# DC-Brush-Motor.net
KiCad netlist of a schematic drawn in Altium Designer
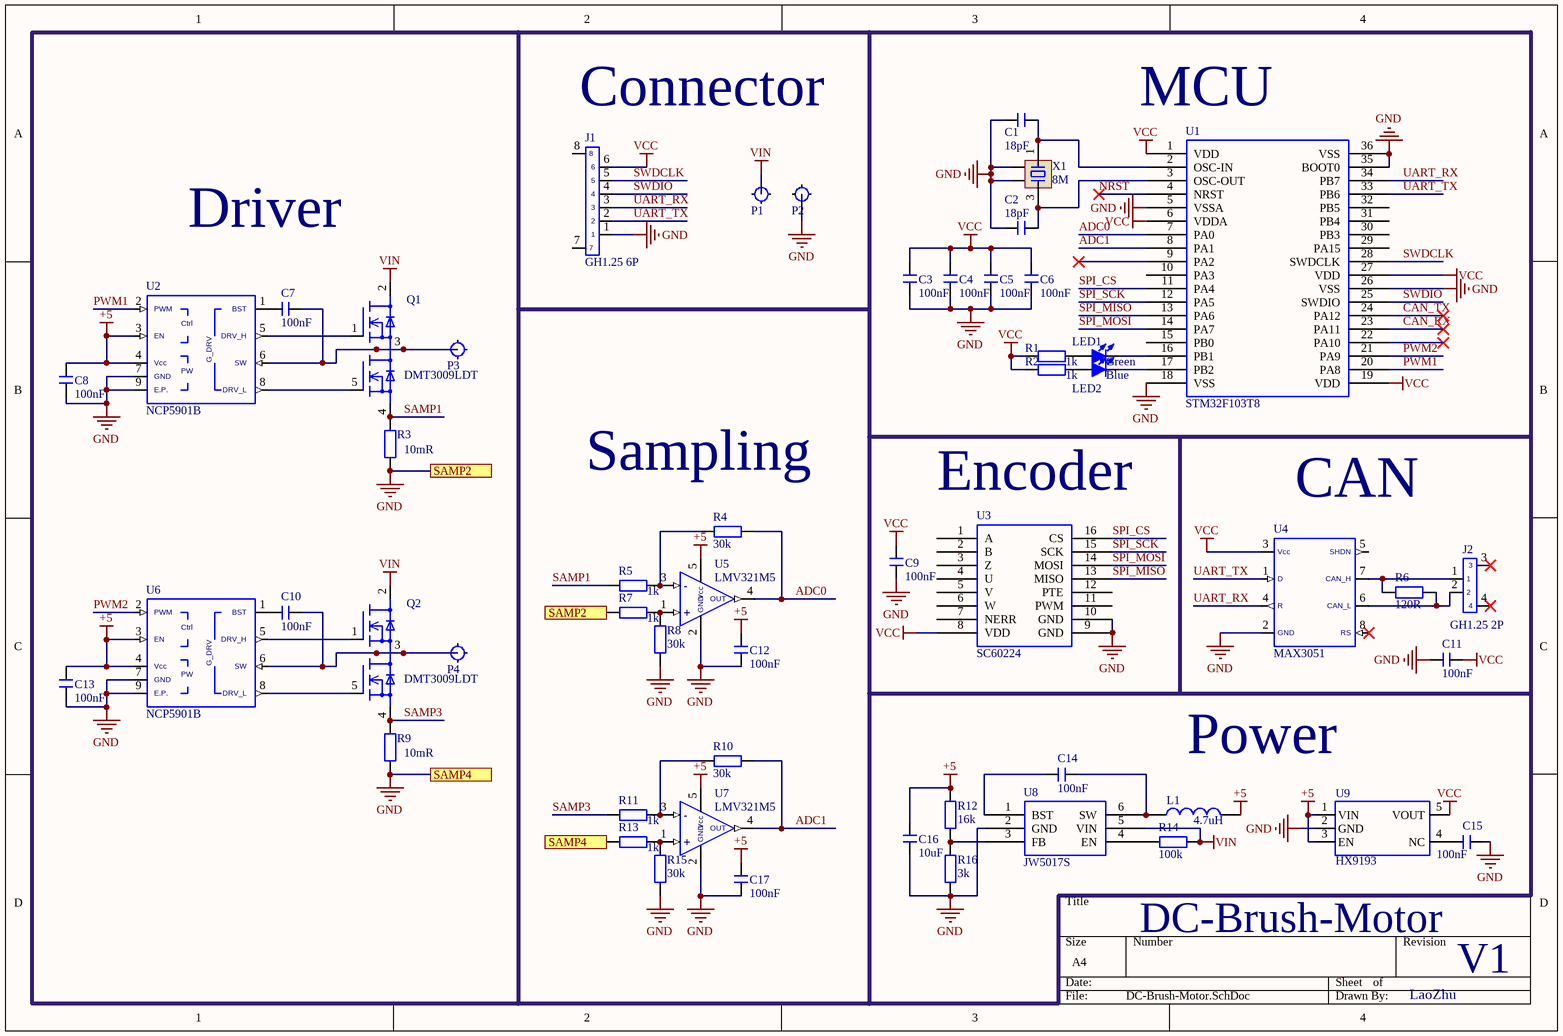
[diagram p0: DC-Brush-Motor.SchDoc]

(export (version "E")
  (design (tool "Eeschema 10.0.6"))
  (components
    (comp (ref "C1")
      (value "18pF")
      (footprint "C 0603")
      (description "无极性贴片电容")
      (fields (field (name "Comment") "C"))
      (libsource (lib "电阻-电容-电感") (part "C"))
    )
    (comp (ref "C2")
      (value "18pF")
      (footprint "C 0603")
      (description "无极性贴片电容")
      (fields (field (name "Comment") "C"))
      (libsource (lib "电阻-电容-电感") (part "C"))
    )
    (comp (ref "C3")
      (value "100nF")
      (footprint "C 0603")
      (description "无极性贴片电容")
      (fields (field (name "Comment") "C"))
      (libsource (lib "电阻-电容-电感") (part "C"))
    )
    (comp (ref "C4")
      (value "100nF")
      (footprint "C 0603")
      (description "无极性贴片电容")
      (fields (field (name "Comment") "C"))
      (libsource (lib "电阻-电容-电感") (part "C"))
    )
    (comp (ref "C5")
      (value "100nF")
      (footprint "C 0603")
      (description "无极性贴片电容")
      (fields (field (name "Comment") "C"))
      (libsource (lib "电阻-电容-电感") (part "C"))
    )
    (comp (ref "C6")
      (value "100nF")
      (footprint "C 0603")
      (description "无极性贴片电容")
      (fields (field (name "Comment") "C"))
      (libsource (lib "电阻-电容-电感") (part "C"))
    )
    (comp (ref "C7")
      (value "100nF")
      (footprint "C 0603")
      (description "无极性贴片电容")
      (fields (field (name "Comment") "C"))
      (libsource (lib "电阻-电容-电感") (part "C"))
    )
    (comp (ref "C8")
      (value "100nF")
      (footprint "C 0603")
      (description "无极性贴片电容")
      (fields (field (name "Comment") "C"))
      (libsource (lib "电阻-电容-电感") (part "C"))
    )
    (comp (ref "C9")
      (value "100nF")
      (footprint "C 0603")
      (description "无极性贴片电容")
      (fields (field (name "Comment") "C"))
      (libsource (lib "电阻-电容-电感") (part "C"))
    )
    (comp (ref "C10")
      (value "100nF")
      (footprint "C 0603")
      (description "无极性贴片电容")
      (fields (field (name "Comment") "C"))
      (libsource (lib "电阻-电容-电感") (part "C"))
    )
    (comp (ref "C11")
      (value "100nF")
      (footprint "C 0603")
      (description "无极性贴片电容")
      (fields (field (name "Comment") "C"))
      (libsource (lib "电阻-电容-电感") (part "C"))
    )
    (comp (ref "C12")
      (value "100nF")
      (footprint "C 0603")
      (description "无极性贴片电容")
      (fields (field (name "Comment") "C"))
      (libsource (lib "电阻-电容-电感") (part "C"))
    )
    (comp (ref "C13")
      (value "100nF")
      (footprint "C 0603")
      (description "无极性贴片电容")
      (fields (field (name "Comment") "C"))
      (libsource (lib "电阻-电容-电感") (part "C"))
    )
    (comp (ref "C14")
      (value "100nF")
      (footprint "C 0603")
      (description "无极性贴片电容")
      (fields (field (name "Comment") "C"))
      (libsource (lib "电阻-电容-电感") (part "C"))
    )
    (comp (ref "C15")
      (value "100nF")
      (footprint "C 0603")
      (description "无极性贴片电容")
      (fields (field (name "Comment") "C"))
      (libsource (lib "电阻-电容-电感") (part "C"))
    )
    (comp (ref "C16")
      (value "10uF")
      (footprint "C 0603")
      (description "无极性贴片电容")
      (fields (field (name "Comment") "C"))
      (libsource (lib "电阻-电容-电感") (part "C"))
    )
    (comp (ref "C17")
      (value "100nF")
      (footprint "C 0603")
      (description "无极性贴片电容")
      (fields (field (name "Comment") "C"))
      (libsource (lib "电阻-电容-电感") (part "C"))
    )
    (comp (ref "J1")
      (value "GH1.25 6P")
      (footprint "GH1.25-6P")
      (libsource (lib "ADlib @LAN") (part "CON_GH1.25_6P"))
    )
    (comp (ref "J2")
      (value "GH1.25 2P")
      (footprint "GH1.25-2P")
      (libsource (lib "ADlib @LAN") (part "CON_GH1.25_2P"))
    )
    (comp (ref "L1")
      (value "4.7uH")
      (footprint "M2520L")
      (description "小功率贴片电感")
      (fields (field (name "Comment") "L"))
      (libsource (lib "电阻-电容-电感") (part "L"))
    )
    (comp (ref "LED1")
      (value "Green")
      (footprint "LED 0603W")
      (description "贴片LED")
      (fields (field (name "版权归属") "源创客"))
      (libsource (lib "LED") (part "LED-SMD"))
    )
    (comp (ref "LED2")
      (value "Blue")
      (footprint "LED 0603W")
      (description "贴片LED")
      (fields (field (name "版权归属") "源创客"))
      (libsource (lib "LED") (part "LED-SMD"))
    )
    (comp (ref "P1")
      (value "CON_Single")
      (footprint "SIG_PAD")
      (libsource (lib "ADlib @LAN") (part "CON_Single"))
    )
    (comp (ref "P2")
      (value "CON_Single")
      (footprint "SIG_PAD")
      (libsource (lib "ADlib @LAN") (part "CON_Single"))
    )
    (comp (ref "P3")
      (value "CON_Single")
      (footprint "4.8MM 冷压端子")
      (libsource (lib "ADlib @LAN") (part "CON_Single"))
    )
    (comp (ref "P4")
      (value "CON_Single")
      (footprint "4.8MM 冷压端子")
      (libsource (lib "ADlib @LAN") (part "CON_Single"))
    )
    (comp (ref "Q1")
      (value "DMT3009LDT")
      (footprint "DFN-8 3X3 (TYPE-K)")
      (libsource (lib "ADlib @LAN") (part "Q_FET_Nx2"))
    )
    (comp (ref "Q2")
      (value "DMT3009LDT")
      (footprint "DFN-8 3X3 (TYPE-K)")
      (libsource (lib "ADlib @LAN") (part "Q_FET_Nx2"))
    )
    (comp (ref "R1")
      (value "1k")
      (footprint "R 0603")
      (description "贴片电阻")
      (fields (field (name "Comment") "R"))
      (libsource (lib "电阻-电容-电感") (part "R"))
    )
    (comp (ref "R2")
      (value "1k")
      (footprint "R 0603")
      (description "贴片电阻")
      (fields (field (name "Comment") "R"))
      (libsource (lib "电阻-电容-电感") (part "R"))
    )
    (comp (ref "R3")
      (value "10mR")
      (footprint "R 1206-HP")
      (description "贴片电阻")
      (fields (field (name "Comment") "R"))
      (libsource (lib "电阻-电容-电感") (part "R"))
    )
    (comp (ref "R4")
      (value "30k")
      (footprint "R 0603")
      (description "贴片电阻")
      (fields (field (name "Comment") "R"))
      (libsource (lib "电阻-电容-电感") (part "R"))
    )
    (comp (ref "R5")
      (value "1k")
      (footprint "R 0603")
      (description "贴片电阻")
      (fields (field (name "Comment") "R"))
      (libsource (lib "电阻-电容-电感") (part "R"))
    )
    (comp (ref "R6")
      (value "120R")
      (footprint "R 0603")
      (description "贴片电阻")
      (fields (field (name "Comment") "R"))
      (libsource (lib "电阻-电容-电感") (part "R"))
    )
    (comp (ref "R7")
      (value "1k")
      (footprint "R 0603")
      (description "贴片电阻")
      (fields (field (name "Comment") "R"))
      (libsource (lib "电阻-电容-电感") (part "R"))
    )
    (comp (ref "R8")
      (value "30k")
      (footprint "R 0603")
      (description "贴片电阻")
      (fields (field (name "Comment") "R"))
      (libsource (lib "电阻-电容-电感") (part "R"))
    )
    (comp (ref "R9")
      (value "10mR")
      (footprint "R 1206-HP")
      (description "贴片电阻")
      (fields (field (name "Comment") "R"))
      (libsource (lib "电阻-电容-电感") (part "R"))
    )
    (comp (ref "R10")
      (value "30k")
      (footprint "R 0603")
      (description "贴片电阻")
      (fields (field (name "Comment") "R"))
      (libsource (lib "电阻-电容-电感") (part "R"))
    )
    (comp (ref "R11")
      (value "1k")
      (footprint "R 0603")
      (description "贴片电阻")
      (fields (field (name "Comment") "R"))
      (libsource (lib "电阻-电容-电感") (part "R"))
    )
    (comp (ref "R12")
      (value "16k")
      (footprint "R 0603")
      (description "贴片电阻")
      (fields (field (name "Comment") "R"))
      (libsource (lib "电阻-电容-电感") (part "R"))
    )
    (comp (ref "R13")
      (value "1k")
      (footprint "R 0603")
      (description "贴片电阻")
      (fields (field (name "Comment") "R"))
      (libsource (lib "电阻-电容-电感") (part "R"))
    )
    (comp (ref "R14")
      (value "100k")
      (footprint "R 0603")
      (description "贴片电阻")
      (fields (field (name "Comment") "R"))
      (libsource (lib "电阻-电容-电感") (part "R"))
    )
    (comp (ref "R15")
      (value "30k")
      (footprint "R 0603")
      (description "贴片电阻")
      (fields (field (name "Comment") "R"))
      (libsource (lib "电阻-电容-电感") (part "R"))
    )
    (comp (ref "R16")
      (value "3k")
      (footprint "R 0603")
      (description "贴片电阻")
      (fields (field (name "Comment") "R"))
      (libsource (lib "电阻-电容-电感") (part "R"))
    )
    (comp (ref "U1")
      (value "STM32F103T8")
      (footprint "QFN-36")
      (libsource (lib "Acme-FOC-V1") (part "STM32F103T8"))
    )
    (comp (ref "U2")
      (value "NCP5901B")
      (footprint "DFN-8")
      (libsource (lib "ADlib @LAN") (part "U_FETs_DVR"))
    )
    (comp (ref "U3") (value "SC60224") (footprint "SSOP16") (libsource (lib "Acme-FOC-V1") (part "SC60224")))
    (comp (ref "U4")
      (value "MAX3051")
      (footprint "SOT23-8L")
      (libsource (lib "ADlib @LAN") (part "U_CAN_TRANS#1"))
    )
    (comp (ref "U5") (value "LMV321M5") (footprint "SOT23-5L") (libsource (lib "ADlib @LAN") (part "U_AMP")))
    (comp (ref "U6")
      (value "NCP5901B")
      (footprint "DFN-8")
      (libsource (lib "ADlib @LAN") (part "U_FETs_DVR"))
    )
    (comp (ref "U7") (value "LMV321M5") (footprint "SOT23-5N") (libsource (lib "ADlib @LAN") (part "U_AMP")))
    (comp (ref "U8")
      (value "JW5017S")
      (footprint "SOT23-6L")
      (libsource (lib "Acme-FOC-V1") (part "JW5017S"))
    )
    (comp (ref "U9")
      (value "HX9193")
      (footprint "SOT23-5L")
      (description "Buck降压芯片")
      (libsource (lib "IC芯片") (part "HX9193"))
    )
    (comp (ref "X1")
      (value "8M")
      (footprint "XTAL-3225")
      (description "4脚晶振")
      (fields (field (name "版权归属") "源创客"))
      (libsource (lib "保险丝-晶振") (part "XTAL-4"))
    )
  )
  (nets
    (net (code "1") (name "+5") (class "Default")
      (node (ref "C12") (pin "2") (pinfunction "2_2") (pintype "passive"))
      (node (ref "C13") (pin "2") (pinfunction "2_2") (pintype "passive"))
      (node (ref "C16") (pin "1") (pinfunction "1_1") (pintype "passive"))
      (node (ref "C17") (pin "2") (pinfunction "2_2") (pintype "passive"))
      (node (ref "C8") (pin "2") (pinfunction "2_2") (pintype "passive"))
      (node (ref "L1") (pin "2") (pinfunction "2_2") (pintype "passive"))
      (node (ref "R12") (pin "1") (pinfunction "1_1") (pintype "passive"))
      (node (ref "U2") (pin "3") (pinfunction "EN_3") (pintype "input"))
      (node (ref "U2") (pin "4") (pinfunction "Vcc_4") (pintype "power_in"))
      (node (ref "U5") (pin "5") (pinfunction "Vcc_5") (pintype "power_in"))
      (node (ref "U6") (pin "3") (pinfunction "EN_3") (pintype "input"))
      (node (ref "U6") (pin "4") (pinfunction "Vcc_4") (pintype "power_in"))
      (node (ref "U7") (pin "5") (pinfunction "Vcc_5") (pintype "power_in"))
      (node (ref "U9") (pin "1") (pinfunction "VIN_1") (pintype "power_in"))
      (node (ref "U9") (pin "3") (pinfunction "EN_3") (pintype "power_in"))
    )
    (net (code "2") (name "/ADC0") (class "Default")
      (node (ref "R4") (pin "2") (pinfunction "2_2") (pintype "passive"))
      (node (ref "U1") (pin "7") (pinfunction "PA0_7") (pintype "passive"))
      (node (ref "U5") (pin "4") (pinfunction "OUT_4") (pintype "output"))
    )
    (net (code "3") (name "/ADC1") (class "Default")
      (node (ref "R10") (pin "2") (pinfunction "2_2") (pintype "passive"))
      (node (ref "U1") (pin "8") (pinfunction "PA1_8") (pintype "passive"))
      (node (ref "U7") (pin "4") (pinfunction "OUT_4") (pintype "output"))
    )
    (net (code "4") (name "/CAN_RX") (class "Default")
      (node (ref "U1") (pin "23") (pinfunction "PA11_23") (pintype "passive+no_connect"))
    )
    (net (code "5") (name "/CAN_TX") (class "Default")
      (node (ref "U1") (pin "24") (pinfunction "PA12_24") (pintype "passive+no_connect"))
    )
    (net (code "6") (name "/NRST") (class "Default")
      (node (ref "U1") (pin "4") (pinfunction "NRST_4") (pintype "passive+no_connect"))
    )
    (net (code "7") (name "/PWM1") (class "Default")
      (node (ref "U1") (pin "20") (pinfunction "PA8_20") (pintype "passive"))
      (node (ref "U2") (pin "2") (pinfunction "PWM_2") (pintype "input"))
    )
    (net (code "8") (name "/PWM2") (class "Default")
      (node (ref "U1") (pin "21") (pinfunction "PA9_21") (pintype "passive"))
      (node (ref "U6") (pin "2") (pinfunction "PWM_2") (pintype "input"))
    )
    (net (code "9") (name "/SAMP1") (class "Default")
      (node (ref "Q1") (pin "4") (pinfunction "S2_4") (pintype "bidirectional"))
      (node (ref "R3") (pin "1") (pinfunction "1_1") (pintype "passive"))
      (node (ref "R5") (pin "1") (pinfunction "1_1") (pintype "passive"))
    )
    (net (code "10") (name "/SAMP3") (class "Default")
      (node (ref "Q2") (pin "4") (pinfunction "S2_4") (pintype "bidirectional"))
      (node (ref "R11") (pin "1") (pinfunction "1_1") (pintype "passive"))
      (node (ref "R9") (pin "1") (pinfunction "1_1") (pintype "passive"))
    )
    (net (code "11") (name "/SPI_CS") (class "Default")
      (node (ref "U1") (pin "11") (pinfunction "PA4_11") (pintype "passive"))
      (node (ref "U3") (pin "16") (pinfunction "CS_16") (pintype "passive"))
    )
    (net (code "12") (name "/SPI_MISO") (class "Default")
      (node (ref "U1") (pin "13") (pinfunction "PA6_13") (pintype "passive"))
      (node (ref "U3") (pin "13") (pinfunction "MISO_13") (pintype "passive"))
    )
    (net (code "13") (name "/SPI_MOSI") (class "Default")
      (node (ref "U1") (pin "14") (pinfunction "PA7_14") (pintype "passive"))
      (node (ref "U3") (pin "14") (pinfunction "MOSI_14") (pintype "passive"))
    )
    (net (code "14") (name "/SPI_SCK") (class "Default")
      (node (ref "U1") (pin "12") (pinfunction "PA5_12") (pintype "passive"))
      (node (ref "U3") (pin "15") (pinfunction "SCK_15") (pintype "passive"))
    )
    (net (code "15") (name "/SWDCLK") (class "Default")
      (node (ref "J1") (pin "5") (pinfunction "5_5") (pintype "bidirectional"))
      (node (ref "U1") (pin "28") (pinfunction "SWDCLK_28") (pintype "passive"))
    )
    (net (code "16") (name "/SWDIO") (class "Default")
      (node (ref "J1") (pin "4") (pinfunction "4_4") (pintype "bidirectional"))
      (node (ref "U1") (pin "25") (pinfunction "SWDIO_25") (pintype "passive"))
    )
    (net (code "17") (name "/UART_RX") (class "Default")
      (node (ref "J1") (pin "3") (pinfunction "3_3") (pintype "bidirectional"))
      (node (ref "U1") (pin "34") (pinfunction "PB7_34") (pintype "passive"))
      (node (ref "U4") (pin "4") (pinfunction "R_4") (pintype "output"))
    )
    (net (code "18") (name "/UART_TX") (class "Default")
      (node (ref "J1") (pin "2") (pinfunction "2_2") (pintype "bidirectional"))
      (node (ref "U1") (pin "33") (pinfunction "PB6_33") (pintype "passive"))
      (node (ref "U4") (pin "1") (pinfunction "D_1") (pintype "input"))
    )
    (net (code "19") (name "GND") (class "Default")
      (node (ref "C1") (pin "1") (pinfunction "1_1") (pintype "passive"))
      (node (ref "C11") (pin "1") (pinfunction "1_1") (pintype "passive"))
      (node (ref "C12") (pin "1") (pinfunction "1_1") (pintype "passive"))
      (node (ref "C13") (pin "1") (pinfunction "1_1") (pintype "passive"))
      (node (ref "C15") (pin "2") (pinfunction "2_2") (pintype "passive"))
      (node (ref "C16") (pin "2") (pinfunction "2_2") (pintype "passive"))
      (node (ref "C17") (pin "1") (pinfunction "1_1") (pintype "passive"))
      (node (ref "C2") (pin "1") (pinfunction "1_1") (pintype "passive"))
      (node (ref "C3") (pin "1") (pinfunction "1_1") (pintype "passive"))
      (node (ref "C4") (pin "1") (pinfunction "1_1") (pintype "passive"))
      (node (ref "C5") (pin "1") (pinfunction "1_1") (pintype "passive"))
      (node (ref "C6") (pin "1") (pinfunction "1_1") (pintype "passive"))
      (node (ref "C8") (pin "1") (pinfunction "1_1") (pintype "passive"))
      (node (ref "C9") (pin "1") (pinfunction "1_1") (pintype "passive"))
      (node (ref "J1") (pin "1") (pinfunction "1_1") (pintype "bidirectional"))
      (node (ref "P2") (pin "0") (pinfunction "0_0") (pintype "passive"))
      (node (ref "R13") (pin "1") (pinfunction "1_1") (pintype "passive"))
      (node (ref "R15") (pin "1") (pinfunction "1_1") (pintype "passive"))
      (node (ref "R16") (pin "1") (pinfunction "1_1") (pintype "passive"))
      (node (ref "R3") (pin "2") (pinfunction "2_2") (pintype "passive"))
      (node (ref "R7") (pin "1") (pinfunction "1_1") (pintype "passive"))
      (node (ref "R8") (pin "1") (pinfunction "1_1") (pintype "passive"))
      (node (ref "R9") (pin "2") (pinfunction "2_2") (pintype "passive"))
      (node (ref "U1") (pin "18") (pinfunction "VSS_18") (pintype "passive"))
      (node (ref "U1") (pin "26") (pinfunction "VSS_26") (pintype "passive"))
      (node (ref "U1") (pin "35") (pinfunction "BOOT0_35") (pintype "passive"))
      (node (ref "U1") (pin "36") (pinfunction "VSS_36") (pintype "passive"))
      (node (ref "U1") (pin "5") (pinfunction "VSSA_5") (pintype "passive"))
      (node (ref "U2") (pin "7") (pinfunction "GND_7") (pintype "power_in"))
      (node (ref "U2") (pin "9") (pinfunction "E.P._9") (pintype "power_in"))
      (node (ref "U3") (pin "10") (pinfunction "GND_10") (pintype "passive"))
      (node (ref "U3") (pin "9") (pinfunction "GND_9") (pintype "passive"))
      (node (ref "U4") (pin "2") (pinfunction "GND_2") (pintype "power_in"))
      (node (ref "U5") (pin "2") (pinfunction "GND_2") (pintype "power_in"))
      (node (ref "U6") (pin "7") (pinfunction "GND_7") (pintype "power_in"))
      (node (ref "U6") (pin "9") (pinfunction "E.P._9") (pintype "power_in"))
      (node (ref "U7") (pin "2") (pinfunction "GND_2") (pintype "power_in"))
      (node (ref "U8") (pin "2") (pinfunction "GND_2") (pintype "passive"))
      (node (ref "U9") (pin "2") (pinfunction "GND_2") (pintype "power_in"))
      (node (ref "X1") (pin "2") (pinfunction "2_2") (pintype "passive"))
      (node (ref "X1") (pin "4") (pinfunction "4_4") (pintype "passive"))
    )
    (net (code "20") (name "Net-(LED1-A)") (class "Default")
      (node (ref "LED1") (pin "1") (pinfunction "A_1") (pintype "passive"))
      (node (ref "R1") (pin "2") (pinfunction "2_2") (pintype "passive"))
    )
    (net (code "21") (name "Net-(LED1-K)") (class "Default")
      (node (ref "LED1") (pin "2") (pinfunction "K_2") (pintype "passive"))
      (node (ref "U1") (pin "16") (pinfunction "PB1_16") (pintype "passive"))
    )
    (net (code "22") (name "Net-(LED2-A)") (class "Default")
      (node (ref "LED2") (pin "1") (pinfunction "A_1") (pintype "passive"))
      (node (ref "R2") (pin "2") (pinfunction "2_2") (pintype "passive"))
    )
    (net (code "23") (name "Net-(LED2-K)") (class "Default")
      (node (ref "LED2") (pin "2") (pinfunction "K_2") (pintype "passive"))
      (node (ref "U1") (pin "17") (pinfunction "PB2_17") (pintype "passive"))
    )
    (net (code "24") (name "Net-(Q1-G1)") (class "Default")
      (node (ref "Q1") (pin "1") (pinfunction "G1_1") (pintype "bidirectional"))
      (node (ref "U2") (pin "5") (pinfunction "DRV_H_5") (pintype "output"))
    )
    (net (code "25") (name "Net-(Q1-G2)") (class "Default")
      (node (ref "Q1") (pin "5") (pinfunction "G2_5") (pintype "bidirectional"))
      (node (ref "U2") (pin "8") (pinfunction "DRV_L_8") (pintype "output"))
    )
    (net (code "26") (name "Net-(Q1-S1{slash}D2)") (class "Default")
      (node (ref "C7") (pin "2") (pinfunction "2_2") (pintype "passive"))
      (node (ref "P3") (pin "0") (pinfunction "0_0") (pintype "passive"))
      (node (ref "Q1") (pin "3") (pinfunction "S1/D2_3") (pintype "bidirectional"))
      (node (ref "U2") (pin "6") (pinfunction "SW_6") (pintype "input"))
    )
    (net (code "27") (name "Net-(Q2-G1)") (class "Default")
      (node (ref "Q2") (pin "1") (pinfunction "G1_1") (pintype "bidirectional"))
      (node (ref "U6") (pin "5") (pinfunction "DRV_H_5") (pintype "output"))
    )
    (net (code "28") (name "Net-(Q2-G2)") (class "Default")
      (node (ref "Q2") (pin "5") (pinfunction "G2_5") (pintype "bidirectional"))
      (node (ref "U6") (pin "8") (pinfunction "DRV_L_8") (pintype "output"))
    )
    (net (code "29") (name "Net-(Q2-S1{slash}D2)") (class "Default")
      (node (ref "C10") (pin "2") (pinfunction "2_2") (pintype "passive"))
      (node (ref "P4") (pin "0") (pinfunction "0_0") (pintype "passive"))
      (node (ref "Q2") (pin "3") (pinfunction "S1/D2_3") (pintype "bidirectional"))
      (node (ref "U6") (pin "6") (pinfunction "SW_6") (pintype "input"))
    )
    (net (code "30") (name "Net-(U1-OSC-IN)") (class "Default")
      (node (ref "C1") (pin "2") (pinfunction "2_2") (pintype "passive"))
      (node (ref "U1") (pin "2") (pinfunction "OSC-IN_2") (pintype "passive"))
      (node (ref "X1") (pin "1") (pinfunction "1_1") (pintype "passive"))
    )
    (net (code "31") (name "Net-(U1-OSC-OUT)") (class "Default")
      (node (ref "C2") (pin "2") (pinfunction "2_2") (pintype "passive"))
      (node (ref "U1") (pin "3") (pinfunction "OSC-OUT_3") (pintype "passive"))
      (node (ref "X1") (pin "3") (pinfunction "3_3") (pintype "passive"))
    )
    (net (code "32") (name "Net-(U2-BST)") (class "Default")
      (node (ref "C7") (pin "1") (pinfunction "1_1") (pintype "passive"))
      (node (ref "U2") (pin "1") (pinfunction "BST_1") (pintype "passive"))
    )
    (net (code "33") (name "Net-(U4-CAN_H)") (class "Default")
      (node (ref "J2") (pin "1") (pinfunction "1_1") (pintype "bidirectional"))
      (node (ref "R6") (pin "1") (pinfunction "1_1") (pintype "passive"))
      (node (ref "U4") (pin "7") (pinfunction "CAN_H_7") (pintype "bidirectional"))
    )
    (net (code "34") (name "Net-(U4-CAN_L)") (class "Default")
      (node (ref "J2") (pin "2") (pinfunction "2_2") (pintype "bidirectional"))
      (node (ref "R6") (pin "2") (pinfunction "2_2") (pintype "passive"))
      (node (ref "U4") (pin "6") (pinfunction "CAN_L_6") (pintype "bidirectional"))
    )
    (net (code "35") (name "Net-(U5-+)") (class "Default")
      (node (ref "R7") (pin "2") (pinfunction "2_2") (pintype "passive"))
      (node (ref "R8") (pin "2") (pinfunction "2_2") (pintype "passive"))
      (node (ref "U5") (pin "1") (pinfunction "+_1") (pintype "input"))
    )
    (net (code "36") (name "Net-(U5--)") (class "Default")
      (node (ref "R4") (pin "1") (pinfunction "1_1") (pintype "passive"))
      (node (ref "R5") (pin "2") (pinfunction "2_2") (pintype "passive"))
      (node (ref "U5") (pin "3") (pinfunction "-_3") (pintype "input"))
    )
    (net (code "37") (name "Net-(U6-BST)") (class "Default")
      (node (ref "C10") (pin "1") (pinfunction "1_1") (pintype "passive"))
      (node (ref "U6") (pin "1") (pinfunction "BST_1") (pintype "passive"))
    )
    (net (code "38") (name "Net-(U7-+)") (class "Default")
      (node (ref "R13") (pin "2") (pinfunction "2_2") (pintype "passive"))
      (node (ref "R15") (pin "2") (pinfunction "2_2") (pintype "passive"))
      (node (ref "U7") (pin "1") (pinfunction "+_1") (pintype "input"))
    )
    (net (code "39") (name "Net-(U7--)") (class "Default")
      (node (ref "R10") (pin "1") (pinfunction "1_1") (pintype "passive"))
      (node (ref "R11") (pin "2") (pinfunction "2_2") (pintype "passive"))
      (node (ref "U7") (pin "3") (pinfunction "-_3") (pintype "input"))
    )
    (net (code "40") (name "Net-(U8-BST)") (class "Default")
      (node (ref "C14") (pin "2") (pinfunction "2_2") (pintype "passive"))
      (node (ref "U8") (pin "1") (pinfunction "BST_1") (pintype "passive"))
    )
    (net (code "41") (name "Net-(U8-EN)") (class "Default")
      (node (ref "R14") (pin "1") (pinfunction "1_1") (pintype "passive"))
      (node (ref "U8") (pin "4") (pinfunction "EN_4") (pintype "passive"))
    )
    (net (code "42") (name "Net-(U8-FB)") (class "Default")
      (node (ref "R12") (pin "2") (pinfunction "2_2") (pintype "passive"))
      (node (ref "R16") (pin "2") (pinfunction "2_2") (pintype "passive"))
      (node (ref "U8") (pin "3") (pinfunction "FB_3") (pintype "passive"))
    )
    (net (code "43") (name "Net-(U8-SW)") (class "Default")
      (node (ref "C14") (pin "1") (pinfunction "1_1") (pintype "passive"))
      (node (ref "L1") (pin "1") (pinfunction "1_1") (pintype "passive"))
      (node (ref "U8") (pin "6") (pinfunction "SW_6") (pintype "passive"))
    )
    (net (code "44") (name "Net-(U9-NC)") (class "Default")
      (node (ref "C15") (pin "1") (pinfunction "1_1") (pintype "passive"))
      (node (ref "U9") (pin "4") (pinfunction "NC_4") (pintype "power_in"))
    )
    (net (code "45") (name "VCC") (class "Default")
      (node (ref "C11") (pin "2") (pinfunction "2_2") (pintype "passive"))
      (node (ref "C3") (pin "2") (pinfunction "2_2") (pintype "passive"))
      (node (ref "C4") (pin "2") (pinfunction "2_2") (pintype "passive"))
      (node (ref "C5") (pin "2") (pinfunction "2_2") (pintype "passive"))
      (node (ref "C6") (pin "2") (pinfunction "2_2") (pintype "passive"))
      (node (ref "C9") (pin "2") (pinfunction "2_2") (pintype "passive"))
      (node (ref "J1") (pin "6") (pinfunction "6_6") (pintype "bidirectional"))
      (node (ref "R1") (pin "1") (pinfunction "1_1") (pintype "passive"))
      (node (ref "R2") (pin "1") (pinfunction "1_1") (pintype "passive"))
      (node (ref "U1") (pin "1") (pinfunction "VDD_1") (pintype "passive"))
      (node (ref "U1") (pin "19") (pinfunction "VDD_19") (pintype "passive"))
      (node (ref "U1") (pin "27") (pinfunction "VDD_27") (pintype "passive"))
      (node (ref "U1") (pin "6") (pinfunction "VDDA_6") (pintype "passive"))
      (node (ref "U3") (pin "8") (pinfunction "VDD_8") (pintype "passive"))
      (node (ref "U4") (pin "3") (pinfunction "Vcc_3") (pintype "power_in"))
      (node (ref "U9") (pin "5") (pinfunction "VOUT_5") (pintype "power_in"))
    )
    (net (code "46") (name "VIN") (class "Default")
      (node (ref "P1") (pin "0") (pinfunction "0_0") (pintype "passive"))
      (node (ref "Q1") (pin "2") (pinfunction "D1_2") (pintype "bidirectional"))
      (node (ref "Q2") (pin "2") (pinfunction "D1_2") (pintype "bidirectional"))
      (node (ref "R14") (pin "2") (pinfunction "2_2") (pintype "passive"))
      (node (ref "U8") (pin "5") (pinfunction "VIN_5") (pintype "passive"))
    )
    (net (code "47") (name "unconnected-(J1-Pad7)") (class "Default")
      (node (ref "J1") (pin "7") (pinfunction "7_7") (pintype "passive"))
    )
    (net (code "48") (name "unconnected-(J1-Pad8)") (class "Default")
      (node (ref "J1") (pin "8") (pinfunction "8_8") (pintype "passive"))
    )
    (net (code "49") (name "unconnected-(J2-Pad3)") (class "Default")
      (node (ref "J2") (pin "3") (pinfunction "3_3") (pintype "passive+no_connect"))
    )
    (net (code "50") (name "unconnected-(J2-Pad4)") (class "Default")
      (node (ref "J2") (pin "4") (pinfunction "4_4") (pintype "passive+no_connect"))
    )
    (net (code "51") (name "unconnected-(U1-PA2-Pad9)") (class "Default")
      (node (ref "U1") (pin "9") (pinfunction "PA2_9") (pintype "passive+no_connect"))
    )
    (net (code "52") (name "unconnected-(U1-PA3-Pad10)") (class "Default")
      (node (ref "U1") (pin "10") (pinfunction "PA3_10") (pintype "passive"))
    )
    (net (code "53") (name "unconnected-(U1-PA10-Pad22)") (class "Default")
      (node (ref "U1") (pin "22") (pinfunction "PA10_22") (pintype "passive+no_connect"))
    )
    (net (code "54") (name "unconnected-(U1-PA15-Pad29)") (class "Default")
      (node (ref "U1") (pin "29") (pinfunction "PA15_29") (pintype "passive"))
    )
    (net (code "55") (name "unconnected-(U1-PB0-Pad15)") (class "Default")
      (node (ref "U1") (pin "15") (pinfunction "PB0_15") (pintype "passive"))
    )
    (net (code "56") (name "unconnected-(U1-PB3-Pad30)") (class "Default")
      (node (ref "U1") (pin "30") (pinfunction "PB3_30") (pintype "passive"))
    )
    (net (code "57") (name "unconnected-(U1-PB4-Pad31)") (class "Default")
      (node (ref "U1") (pin "31") (pinfunction "PB4_31") (pintype "passive"))
    )
    (net (code "58") (name "unconnected-(U1-PB5-Pad32)") (class "Default")
      (node (ref "U1") (pin "32") (pinfunction "PB5_32") (pintype "passive"))
    )
    (net (code "59") (name "unconnected-(U3-A-Pad1)") (class "Default")
      (node (ref "U3") (pin "1") (pinfunction "A_1") (pintype "passive"))
    )
    (net (code "60") (name "unconnected-(U3-B-Pad2)") (class "Default")
      (node (ref "U3") (pin "2") (pinfunction "B_2") (pintype "passive"))
    )
    (net (code "61") (name "unconnected-(U3-NERR-Pad7)") (class "Default")
      (node (ref "U3") (pin "7") (pinfunction "NERR_7") (pintype "passive"))
    )
    (net (code "62") (name "unconnected-(U3-PTE-Pad12)") (class "Default")
      (node (ref "U3") (pin "12") (pinfunction "PTE_12") (pintype "passive"))
    )
    (net (code "63") (name "unconnected-(U3-PWM-Pad11)") (class "Default")
      (node (ref "U3") (pin "11") (pinfunction "PWM_11") (pintype "passive"))
    )
    (net (code "64") (name "unconnected-(U3-U-Pad4)") (class "Default")
      (node (ref "U3") (pin "4") (pinfunction "U_4") (pintype "passive"))
    )
    (net (code "65") (name "unconnected-(U3-V-Pad5)") (class "Default")
      (node (ref "U3") (pin "5") (pinfunction "V_5") (pintype "passive"))
    )
    (net (code "66") (name "unconnected-(U3-W-Pad6)") (class "Default")
      (node (ref "U3") (pin "6") (pinfunction "W_6") (pintype "passive"))
    )
    (net (code "67") (name "unconnected-(U3-Z-Pad3)") (class "Default")
      (node (ref "U3") (pin "3") (pinfunction "Z_3") (pintype "passive"))
    )
    (net (code "68") (name "unconnected-(U4-RS-Pad8)") (class "Default")
      (node (ref "U4") (pin "8") (pinfunction "RS_8") (pintype "input+no_connect"))
    )
    (net (code "69") (name "unconnected-(U4-SHDN-Pad5)") (class "Default")
      (node (ref "U4") (pin "5") (pinfunction "SHDN_5") (pintype "output"))
    )
  )
)
